# schematic.net
KiCad netlist of a schematic drawn in EAGLE
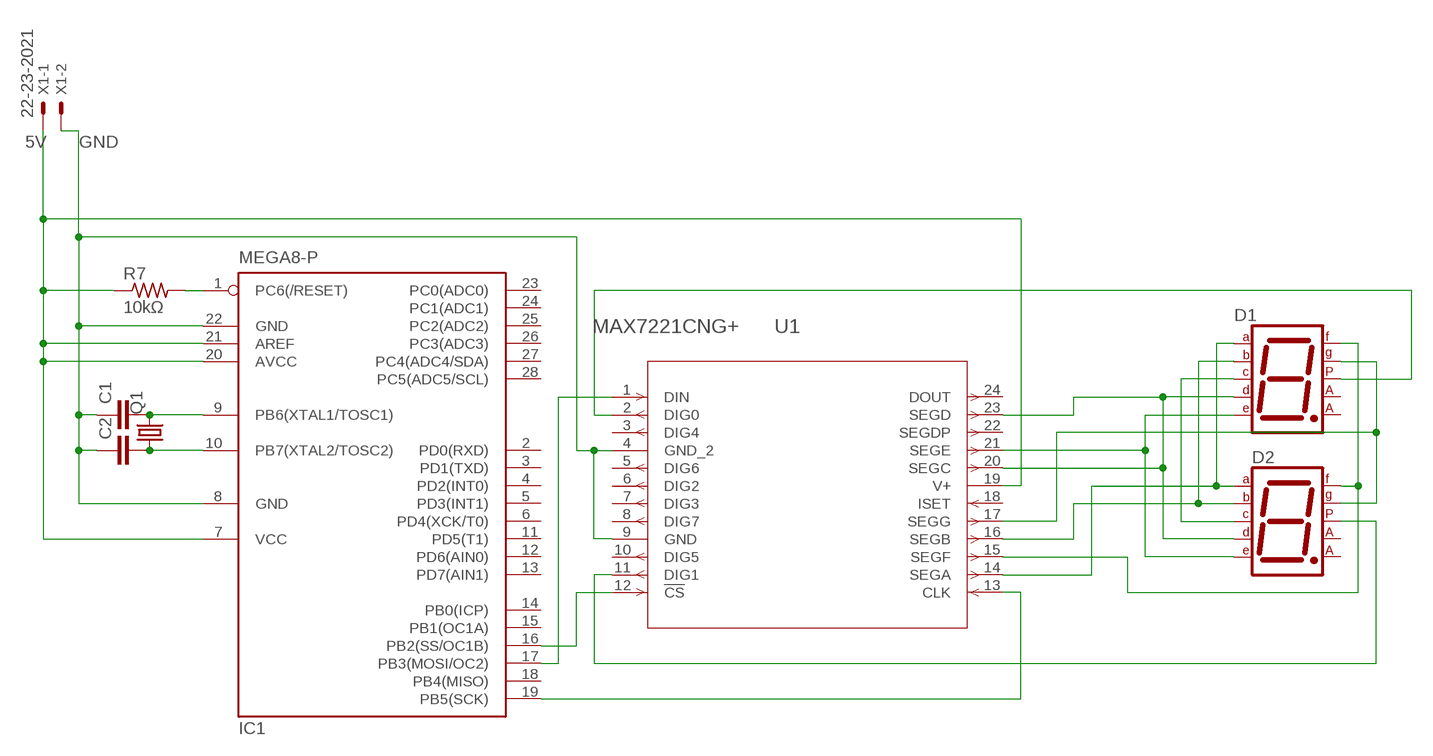
[diagram p0: schematic, sheet 1]

(export (version "E")
  (design (tool "Eeschema 10.0.6"))
  (components
    (comp (ref "C1")
      (value "C2,5-3")
      (footprint "eagle-import:C2.5-3")
      (libsource (lib "eagle-import") (part "C2,5-3"))
    )
    (comp (ref "C2")
      (value "C2,5-3")
      (footprint "eagle-import:C2.5-3")
      (libsource (lib "eagle-import") (part "C2,5-3"))
    )
    (comp (ref "D1")
      (value "7SEG-CA")
      (footprint "eagle-import:7SEG-13")
      (libsource (lib "eagle-import") (part "7SEG-CA"))
    )
    (comp (ref "D2")
      (value "7SEG-CA")
      (footprint "eagle-import:7SEG-13")
      (libsource (lib "eagle-import") (part "7SEG-CA"))
    )
    (comp (ref "IC1")
      (value "MEGA8-P")
      (footprint "eagle-import:DIL28-3")
      (libsource (lib "eagle-import") (part "MEGA8-P"))
    )
    (comp (ref "Q1")
      (value "CRYSTALHC18U-V")
      (footprint "eagle-import:HC18U-V")
      (libsource (lib "eagle-import") (part "CRYSTALHC18U-V"))
    )
    (comp (ref "R7")
      (value "10kΩ")
      (footprint "eagle-import:0204V")
      (libsource (lib "eagle-import") (part "R-US_0204/2V"))
    )
    (comp (ref "U1")
      (value "MAX7221CNG+")
      (footprint "eagle-import:21-0043D_24_MXM")
      (fields (field (name "COPYRIGHT") "Copyright (C) 2022 Ultra Librarian. All rights reserved."))
      (libsource (lib "eagle-import") (part "MAX7221CNG+"))
    )
    (comp (ref "X1")
      (value "22-23-2021")
      (footprint "eagle-import:22-23-2021")
      (fields (field (name "MF") "MOLEX"))
      (libsource (lib "eagle-import") (part "22-23-2021"))
    )
  )
  (nets
    (net (code "1") (name "/5V") (class "Default")
      (node (ref "IC1") (pin "20") (pinfunction "AVCC_20") (pintype "power_in"))
      (node (ref "IC1") (pin "21") (pinfunction "AREF_21") (pintype "passive"))
      (node (ref "IC1") (pin "7") (pinfunction "VCC_7") (pintype "power_in"))
      (node (ref "R7") (pin "1") (pinfunction "1_1") (pintype "passive"))
      (node (ref "U1") (pin "19") (pinfunction "V+_19") (pintype "power_in"))
      (node (ref "X1") (pin "1") (pinfunction "S_1") (pintype "passive"))
    )
    (net (code "2") (name "/GND") (class "Default")
      (node (ref "C1") (pin "1") (pinfunction "1_1") (pintype "passive"))
      (node (ref "C2") (pin "1") (pinfunction "1_1") (pintype "passive"))
      (node (ref "IC1") (pin "22") (pinfunction "GND_22") (pintype "power_in"))
      (node (ref "IC1") (pin "8") (pinfunction "GND_8") (pintype "power_in"))
      (node (ref "U1") (pin "4") (pinfunction "GND_2_4") (pintype "power_in"))
      (node (ref "U1") (pin "9") (pinfunction "GND_9") (pintype "power_in"))
      (node (ref "X1") (pin "2") (pinfunction "S_2") (pintype "passive"))
    )
    (net (code "3") (name "Net-(D1-A)") (class "Default")
      (node (ref "D1") (pin "7") (pinfunction "A_7") (pintype "passive"))
      (node (ref "D2") (pin "7") (pinfunction "A_7") (pintype "passive"))
      (node (ref "U1") (pin "14") (pinfunction "SEGA_14") (pintype "output"))
    )
    (net (code "4") (name "Net-(D1-B)") (class "Default")
      (node (ref "D1") (pin "6") (pinfunction "B_6") (pintype "passive"))
      (node (ref "D2") (pin "6") (pinfunction "B_6") (pintype "passive"))
      (node (ref "U1") (pin "16") (pinfunction "SEGB_16") (pintype "output"))
    )
    (net (code "5") (name "Net-(D1-C)") (class "Default")
      (node (ref "D1") (pin "4") (pinfunction "C_4") (pintype "passive"))
      (node (ref "D2") (pin "4") (pinfunction "C_4") (pintype "passive"))
    )
    (net (code "6") (name "Net-(D1-D)") (class "Default")
      (node (ref "D1") (pin "2") (pinfunction "D_2") (pintype "passive"))
      (node (ref "D2") (pin "2") (pinfunction "D_2") (pintype "passive"))
      (node (ref "U1") (pin "20") (pinfunction "SEGC_20") (pintype "output"))
      (node (ref "U1") (pin "23") (pinfunction "SEGD_23") (pintype "output"))
    )
    (net (code "7") (name "Net-(D1-DP)") (class "Default")
      (node (ref "D1") (pin "5") (pinfunction "DP_5") (pintype "passive"))
      (node (ref "U1") (pin "2") (pinfunction "DIG0_2") (pintype "output"))
    )
    (net (code "8") (name "Net-(D1-E)") (class "Default")
      (node (ref "D1") (pin "1") (pinfunction "E_1") (pintype "passive"))
      (node (ref "D2") (pin "1") (pinfunction "E_1") (pintype "passive"))
      (node (ref "U1") (pin "21") (pinfunction "SEGE_21") (pintype "output"))
    )
    (net (code "9") (name "Net-(D1-F)") (class "Default")
      (node (ref "D1") (pin "9") (pinfunction "F_9") (pintype "passive"))
      (node (ref "D2") (pin "9") (pinfunction "F_9") (pintype "passive"))
      (node (ref "U1") (pin "15") (pinfunction "SEGF_15") (pintype "output"))
    )
    (net (code "10") (name "Net-(D1-G)") (class "Default")
      (node (ref "D1") (pin "10") (pinfunction "G_10") (pintype "passive"))
      (node (ref "D2") (pin "10") (pinfunction "G_10") (pintype "passive"))
      (node (ref "U1") (pin "17") (pinfunction "SEGG_17") (pintype "output"))
    )
    (net (code "11") (name "Net-(D2-DP)") (class "Default")
      (node (ref "D2") (pin "5") (pinfunction "DP_5") (pintype "passive"))
      (node (ref "U1") (pin "11") (pinfunction "DIG1_11") (pintype "output"))
    )
    (net (code "12") (name "Net-(IC1-PB2(SS{slash}OC1B))") (class "Default")
      (node (ref "IC1") (pin "16") (pinfunction "PB2(SS/OC1B)_16") (pintype "bidirectional"))
      (node (ref "U1") (pin "12") (pinfunction "~{CS}_12") (pintype "input"))
    )
    (net (code "13") (name "Net-(IC1-PB3(MOSI{slash}OC2))") (class "Default")
      (node (ref "IC1") (pin "17") (pinfunction "PB3(MOSI/OC2)_17") (pintype "bidirectional"))
      (node (ref "U1") (pin "1") (pinfunction "DIN_1") (pintype "input"))
    )
    (net (code "14") (name "Net-(IC1-PB5(SCK))") (class "Default")
      (node (ref "IC1") (pin "19") (pinfunction "PB5(SCK)_19") (pintype "bidirectional"))
      (node (ref "U1") (pin "13") (pinfunction "CLK_13") (pintype "input"))
    )
    (net (code "15") (name "Net-(IC1-PB6(XTAL1{slash}TOSC1))") (class "Default")
      (node (ref "C1") (pin "2") (pinfunction "2_2") (pintype "passive"))
      (node (ref "IC1") (pin "9") (pinfunction "PB6(XTAL1/TOSC1)_9") (pintype "bidirectional"))
      (node (ref "Q1") (pin "2") (pinfunction "2_2") (pintype "passive"))
    )
    (net (code "16") (name "Net-(IC1-PB7(XTAL2{slash}TOSC2))") (class "Default")
      (node (ref "C2") (pin "2") (pinfunction "2_2") (pintype "passive"))
      (node (ref "IC1") (pin "10") (pinfunction "PB7(XTAL2/TOSC2)_10") (pintype "bidirectional"))
      (node (ref "Q1") (pin "1") (pinfunction "1_1") (pintype "passive"))
    )
    (net (code "17") (name "Net-(IC1-PC6({slash}RESET))") (class "Default")
      (node (ref "IC1") (pin "1") (pinfunction "PC6(/RESET)_1") (pintype "bidirectional"))
      (node (ref "R7") (pin "2") (pinfunction "2_2") (pintype "passive"))
    )
    (net (code "18") (name "unconnected-(D1-CA1-Pad3)") (class "Default")
      (node (ref "D1") (pin "3") (pinfunction "CA1_3") (pintype "passive"))
    )
    (net (code "19") (name "unconnected-(D1-CA2-Pad8)") (class "Default")
      (node (ref "D1") (pin "8") (pinfunction "CA2_8") (pintype "passive"))
    )
    (net (code "20") (name "unconnected-(D2-CA1-Pad3)") (class "Default")
      (node (ref "D2") (pin "3") (pinfunction "CA1_3") (pintype "passive"))
    )
    (net (code "21") (name "unconnected-(D2-CA2-Pad8)") (class "Default")
      (node (ref "D2") (pin "8") (pinfunction "CA2_8") (pintype "passive"))
    )
    (net (code "22") (name "unconnected-(IC1-PB0(ICP)-Pad14)") (class "Default")
      (node (ref "IC1") (pin "14") (pinfunction "PB0(ICP)_14") (pintype "bidirectional"))
    )
    (net (code "23") (name "unconnected-(IC1-PB1(OC1A)-Pad15)") (class "Default")
      (node (ref "IC1") (pin "15") (pinfunction "PB1(OC1A)_15") (pintype "bidirectional"))
    )
    (net (code "24") (name "unconnected-(IC1-PB4(MISO)-Pad18)") (class "Default")
      (node (ref "IC1") (pin "18") (pinfunction "PB4(MISO)_18") (pintype "bidirectional"))
    )
    (net (code "25") (name "unconnected-(IC1-PC0(ADC0)-Pad23)") (class "Default")
      (node (ref "IC1") (pin "23") (pinfunction "PC0(ADC0)_23") (pintype "bidirectional"))
    )
    (net (code "26") (name "unconnected-(IC1-PC1(ADC1)-Pad24)") (class "Default")
      (node (ref "IC1") (pin "24") (pinfunction "PC1(ADC1)_24") (pintype "bidirectional"))
    )
    (net (code "27") (name "unconnected-(IC1-PC2(ADC2)-Pad25)") (class "Default")
      (node (ref "IC1") (pin "25") (pinfunction "PC2(ADC2)_25") (pintype "bidirectional"))
    )
    (net (code "28") (name "unconnected-(IC1-PC3(ADC3)-Pad26)") (class "Default")
      (node (ref "IC1") (pin "26") (pinfunction "PC3(ADC3)_26") (pintype "bidirectional"))
    )
    (net (code "29") (name "unconnected-(IC1-PC4(ADC4{slash}SDA)-Pad27)") (class "Default")
      (node (ref "IC1") (pin "27") (pinfunction "PC4(ADC4/SDA)_27") (pintype "bidirectional"))
    )
    (net (code "30") (name "unconnected-(IC1-PC5(ADC5{slash}SCL)-Pad28)") (class "Default")
      (node (ref "IC1") (pin "28") (pinfunction "PC5(ADC5/SCL)_28") (pintype "bidirectional"))
    )
    (net (code "31") (name "unconnected-(IC1-PD0(RXD)-Pad2)") (class "Default")
      (node (ref "IC1") (pin "2") (pinfunction "PD0(RXD)_2") (pintype "bidirectional"))
    )
    (net (code "32") (name "unconnected-(IC1-PD1(TXD)-Pad3)") (class "Default")
      (node (ref "IC1") (pin "3") (pinfunction "PD1(TXD)_3") (pintype "bidirectional"))
    )
    (net (code "33") (name "unconnected-(IC1-PD2(INT0)-Pad4)") (class "Default")
      (node (ref "IC1") (pin "4") (pinfunction "PD2(INT0)_4") (pintype "bidirectional"))
    )
    (net (code "34") (name "unconnected-(IC1-PD3(INT1)-Pad5)") (class "Default")
      (node (ref "IC1") (pin "5") (pinfunction "PD3(INT1)_5") (pintype "bidirectional"))
    )
    (net (code "35") (name "unconnected-(IC1-PD4(XCK{slash}T0)-Pad6)") (class "Default")
      (node (ref "IC1") (pin "6") (pinfunction "PD4(XCK/T0)_6") (pintype "bidirectional"))
    )
    (net (code "36") (name "unconnected-(IC1-PD5(T1)-Pad11)") (class "Default")
      (node (ref "IC1") (pin "11") (pinfunction "PD5(T1)_11") (pintype "bidirectional"))
    )
    (net (code "37") (name "unconnected-(IC1-PD6(AIN0)-Pad12)") (class "Default")
      (node (ref "IC1") (pin "12") (pinfunction "PD6(AIN0)_12") (pintype "bidirectional"))
    )
    (net (code "38") (name "unconnected-(IC1-PD7(AIN1)-Pad13)") (class "Default")
      (node (ref "IC1") (pin "13") (pinfunction "PD7(AIN1)_13") (pintype "bidirectional"))
    )
    (net (code "39") (name "unconnected-(U1-DIG2-Pad6)") (class "Default")
      (node (ref "U1") (pin "6") (pinfunction "DIG2_6") (pintype "output"))
    )
    (net (code "40") (name "unconnected-(U1-DIG3-Pad7)") (class "Default")
      (node (ref "U1") (pin "7") (pinfunction "DIG3_7") (pintype "output"))
    )
    (net (code "41") (name "unconnected-(U1-DIG4-Pad3)") (class "Default")
      (node (ref "U1") (pin "3") (pinfunction "DIG4_3") (pintype "output"))
    )
    (net (code "42") (name "unconnected-(U1-DIG5-Pad10)") (class "Default")
      (node (ref "U1") (pin "10") (pinfunction "DIG5_10") (pintype "output"))
    )
    (net (code "43") (name "unconnected-(U1-DIG6-Pad5)") (class "Default")
      (node (ref "U1") (pin "5") (pinfunction "DIG6_5") (pintype "output"))
    )
    (net (code "44") (name "unconnected-(U1-DIG7-Pad8)") (class "Default")
      (node (ref "U1") (pin "8") (pinfunction "DIG7_8") (pintype "output"))
    )
    (net (code "45") (name "unconnected-(U1-DOUT-Pad24)") (class "Default")
      (node (ref "U1") (pin "24") (pinfunction "DOUT_24") (pintype "output"))
    )
    (net (code "46") (name "unconnected-(U1-ISET-Pad18)") (class "Default")
      (node (ref "U1") (pin "18") (pinfunction "ISET_18") (pintype "input"))
    )
    (net (code "47") (name "unconnected-(U1-SEGDP-Pad22)") (class "Default")
      (node (ref "U1") (pin "22") (pinfunction "SEGDP_22") (pintype "output"))
    )
  )
)
